# relay.net
KiCad netlist of a schematic drawn in EAGLE
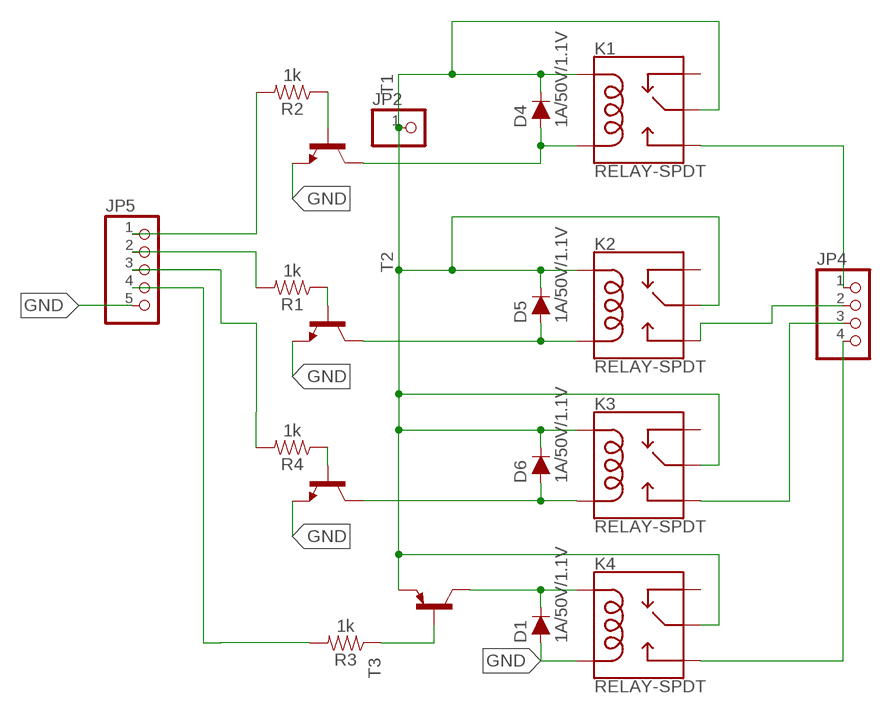
[diagram p0: schematic, sheet 1]

(export (version "E")
  (design (tool "Eeschema 10.0.6"))
  (components
    (comp (ref "D1")
      (value "1A/50V/1.1V")
      (footprint "eagle-import:DIODE-1N4001")
      (libsource (lib "eagle-import") (part "DIODE-PTH"))
    )
    (comp (ref "D4")
      (value "1A/50V/1.1V")
      (footprint "eagle-import:DIODE-1N4001")
      (libsource (lib "eagle-import") (part "DIODE-PTH"))
    )
    (comp (ref "D5")
      (value "1A/50V/1.1V")
      (footprint "eagle-import:DIODE-1N4001")
      (libsource (lib "eagle-import") (part "DIODE-PTH"))
    )
    (comp (ref "D6")
      (value "1A/50V/1.1V")
      (footprint "eagle-import:DIODE-1N4001")
      (libsource (lib "eagle-import") (part "DIODE-PTH"))
    )
    (comp (ref "JP2")
      (value "PINHD-1X1")
      (footprint "eagle-import:1X01")
      (libsource (lib "eagle-import") (part "PINHD-1X1"))
    )
    (comp (ref "JP4")
      (value "PINHD-1X4")
      (footprint "eagle-import:1X04")
      (libsource (lib "eagle-import") (part "PINHD-1X4"))
    )
    (comp (ref "JP5")
      (value "PINHD-1X5")
      (footprint "eagle-import:1X05")
      (libsource (lib "eagle-import") (part "PINHD-1X5"))
    )
    (comp (ref "K1")
      (value "RELAY-SPDT")
      (footprint "eagle-import:RELAY_G5LE")
      (libsource (lib "eagle-import") (part "RELAY-SPDT"))
    )
    (comp (ref "K2")
      (value "RELAY-SPDT")
      (footprint "eagle-import:RELAY_G5LE")
      (libsource (lib "eagle-import") (part "RELAY-SPDT"))
    )
    (comp (ref "K3")
      (value "RELAY-SPDT")
      (footprint "eagle-import:RELAY_G5LE")
      (libsource (lib "eagle-import") (part "RELAY-SPDT"))
    )
    (comp (ref "K4")
      (value "RELAY-SPDT")
      (footprint "eagle-import:RELAY_G5LE")
      (libsource (lib "eagle-import") (part "RELAY-SPDT"))
    )
    (comp (ref "R1")
      (value "1k")
      (footprint "eagle-import:AXIAL-0.3")
      (libsource (lib "eagle-import") (part "1KOHM-HORIZ-1/4W-1%"))
    )
    (comp (ref "R2")
      (value "1k")
      (footprint "eagle-import:AXIAL-0.3")
      (libsource (lib "eagle-import") (part "1KOHM-HORIZ-1/4W-1%"))
    )
    (comp (ref "R3")
      (value "1k")
      (footprint "eagle-import:AXIAL-0.3")
      (libsource (lib "eagle-import") (part "1KOHM-HORIZ-1/4W-1%"))
    )
    (comp (ref "R4")
      (value "1k")
      (footprint "eagle-import:AXIAL-0.3")
      (libsource (lib "eagle-import") (part "1KOHM-HORIZ-1/4W-1%"))
    )
    (comp (ref "T1")
      (value "2N5401-NPN-TO92-CBE")
      (footprint "eagle-import:TO92-CBE")
      (libsource (lib "eagle-import") (part "-NPN-TO92-CBE2N5401"))
    )
    (comp (ref "T2")
      (value "2N5401-NPN-TO92-CBE")
      (footprint "eagle-import:TO92-CBE")
      (fields (field (name "SPICEPREFIX") "J"))
      (libsource (lib "eagle-import") (part "-NPN-TO92-CBE2N5401"))
    )
    (comp (ref "T3")
      (value "2N4126-PNP-TO92-CBE")
      (footprint "eagle-import:TO92-CBE")
      (libsource (lib "eagle-import") (part "-PNP-TO92-CBE2N4126"))
    )
    (comp (ref "T4")
      (value "2N5401-NPN-TO92-CBE")
      (footprint "eagle-import:TO92-CBE")
      (fields (field (name "SPICEPREFIX") "J"))
      (libsource (lib "eagle-import") (part "-NPN-TO92-CBE2N5401"))
    )
  )
  (nets
    (net (code "1") (name "GND") (class "Default")
      (node (ref "D1") (pin "A") (pinfunction "A_A") (pintype "passive"))
      (node (ref "JP5") (pin "5") (pinfunction "5_5") (pintype "passive"))
      (node (ref "K4") (pin "5") (pinfunction "COIL2_5") (pintype "bidirectional"))
      (node (ref "T1") (pin "E") (pinfunction "E_E") (pintype "passive"))
      (node (ref "T2") (pin "E") (pinfunction "E_E") (pintype "passive"))
      (node (ref "T4") (pin "E") (pinfunction "E_E") (pintype "passive"))
    )
    (net (code "2") (name "Net-(K1-COIL1)") (class "Default")
      (node (ref "D4") (pin "C") (pinfunction "C_C") (pintype "passive"))
      (node (ref "D5") (pin "C") (pinfunction "C_C") (pintype "passive"))
      (node (ref "D6") (pin "C") (pinfunction "C_C") (pintype "passive"))
      (node (ref "JP2") (pin "1") (pinfunction "1_1") (pintype "passive"))
      (node (ref "K1") (pin "1") (pinfunction "MAIN_1") (pintype "bidirectional"))
      (node (ref "K1") (pin "2") (pinfunction "COIL1_2") (pintype "bidirectional"))
      (node (ref "K2") (pin "1") (pinfunction "MAIN_1") (pintype "bidirectional"))
      (node (ref "K2") (pin "2") (pinfunction "COIL1_2") (pintype "bidirectional"))
      (node (ref "K3") (pin "1") (pinfunction "MAIN_1") (pintype "bidirectional"))
      (node (ref "K3") (pin "2") (pinfunction "COIL1_2") (pintype "bidirectional"))
      (node (ref "K4") (pin "1") (pinfunction "MAIN_1") (pintype "bidirectional"))
      (node (ref "T3") (pin "E") (pinfunction "E_E") (pintype "passive"))
    )
    (net (code "3") (name "Net-(K1-COIL2)") (class "Default")
      (node (ref "D4") (pin "A") (pinfunction "A_A") (pintype "passive"))
      (node (ref "K1") (pin "5") (pinfunction "COIL2_5") (pintype "bidirectional"))
      (node (ref "T1") (pin "C") (pinfunction "C_C") (pintype "passive"))
    )
    (net (code "4") (name "Net-(K1-NO)") (class "Default")
      (node (ref "JP4") (pin "1") (pinfunction "1_1") (pintype "passive"))
      (node (ref "K1") (pin "3") (pinfunction "NO_3") (pintype "bidirectional"))
    )
    (net (code "5") (name "Net-(K2-COIL2)") (class "Default")
      (node (ref "D5") (pin "A") (pinfunction "A_A") (pintype "passive"))
      (node (ref "K2") (pin "5") (pinfunction "COIL2_5") (pintype "bidirectional"))
      (node (ref "T2") (pin "C") (pinfunction "C_C") (pintype "passive"))
    )
    (net (code "6") (name "Net-(K2-NO)") (class "Default")
      (node (ref "JP4") (pin "2") (pinfunction "2_2") (pintype "passive"))
      (node (ref "K2") (pin "3") (pinfunction "NO_3") (pintype "bidirectional"))
    )
    (net (code "7") (name "Net-(K3-COIL2)") (class "Default")
      (node (ref "D6") (pin "A") (pinfunction "A_A") (pintype "passive"))
      (node (ref "K3") (pin "5") (pinfunction "COIL2_5") (pintype "bidirectional"))
      (node (ref "T4") (pin "C") (pinfunction "C_C") (pintype "passive"))
    )
    (net (code "8") (name "Net-(K3-NO)") (class "Default")
      (node (ref "JP4") (pin "3") (pinfunction "3_3") (pintype "passive"))
      (node (ref "K3") (pin "3") (pinfunction "NO_3") (pintype "bidirectional"))
    )
    (net (code "9") (name "Net-(K4-COIL1)") (class "Default")
      (node (ref "D1") (pin "C") (pinfunction "C_C") (pintype "passive"))
      (node (ref "K4") (pin "2") (pinfunction "COIL1_2") (pintype "bidirectional"))
      (node (ref "T3") (pin "C") (pinfunction "C_C") (pintype "passive"))
    )
    (net (code "10") (name "Net-(K4-NO)") (class "Default")
      (node (ref "JP4") (pin "4") (pinfunction "4_4") (pintype "passive"))
      (node (ref "K4") (pin "3") (pinfunction "NO_3") (pintype "bidirectional"))
    )
    (net (code "11") (name "Net-(R1-1)") (class "Default")
      (node (ref "R1") (pin "P$1") (pinfunction "1_P$1") (pintype "passive"))
      (node (ref "T2") (pin "B") (pinfunction "B_B") (pintype "passive"))
    )
    (net (code "12") (name "Net-(R1-2)") (class "Default")
      (node (ref "JP5") (pin "2") (pinfunction "2_2") (pintype "passive"))
      (node (ref "R1") (pin "P$2") (pinfunction "2_P$2") (pintype "passive"))
    )
    (net (code "13") (name "Net-(R2-1)") (class "Default")
      (node (ref "R2") (pin "P$1") (pinfunction "1_P$1") (pintype "passive"))
      (node (ref "T1") (pin "B") (pinfunction "B_B") (pintype "passive"))
    )
    (net (code "14") (name "Net-(R2-2)") (class "Default")
      (node (ref "JP5") (pin "1") (pinfunction "1_1") (pintype "passive"))
      (node (ref "R2") (pin "P$2") (pinfunction "2_P$2") (pintype "passive"))
    )
    (net (code "15") (name "Net-(R3-1)") (class "Default")
      (node (ref "R3") (pin "P$1") (pinfunction "1_P$1") (pintype "passive"))
      (node (ref "T3") (pin "B") (pinfunction "B_B") (pintype "passive"))
    )
    (net (code "16") (name "Net-(R3-2)") (class "Default")
      (node (ref "JP5") (pin "4") (pinfunction "4_4") (pintype "passive"))
      (node (ref "R3") (pin "P$2") (pinfunction "2_P$2") (pintype "passive"))
    )
    (net (code "17") (name "Net-(R4-1)") (class "Default")
      (node (ref "R4") (pin "P$1") (pinfunction "1_P$1") (pintype "passive"))
      (node (ref "T4") (pin "B") (pinfunction "B_B") (pintype "passive"))
    )
    (net (code "18") (name "Net-(R4-2)") (class "Default")
      (node (ref "JP5") (pin "3") (pinfunction "3_3") (pintype "passive"))
      (node (ref "R4") (pin "P$2") (pinfunction "2_P$2") (pintype "passive"))
    )
    (net (code "19") (name "unconnected-(K1-NC-Pad4)") (class "Default")
      (node (ref "K1") (pin "4") (pinfunction "NC_4") (pintype "bidirectional"))
    )
    (net (code "20") (name "unconnected-(K2-NC-Pad4)") (class "Default")
      (node (ref "K2") (pin "4") (pinfunction "NC_4") (pintype "bidirectional"))
    )
    (net (code "21") (name "unconnected-(K3-NC-Pad4)") (class "Default")
      (node (ref "K3") (pin "4") (pinfunction "NC_4") (pintype "bidirectional"))
    )
    (net (code "22") (name "unconnected-(K4-NC-Pad4)") (class "Default")
      (node (ref "K4") (pin "4") (pinfunction "NC_4") (pintype "bidirectional"))
    )
  )
)
